# design.net
KiCad netlist of a schematic drawn in EasyEDA Pro
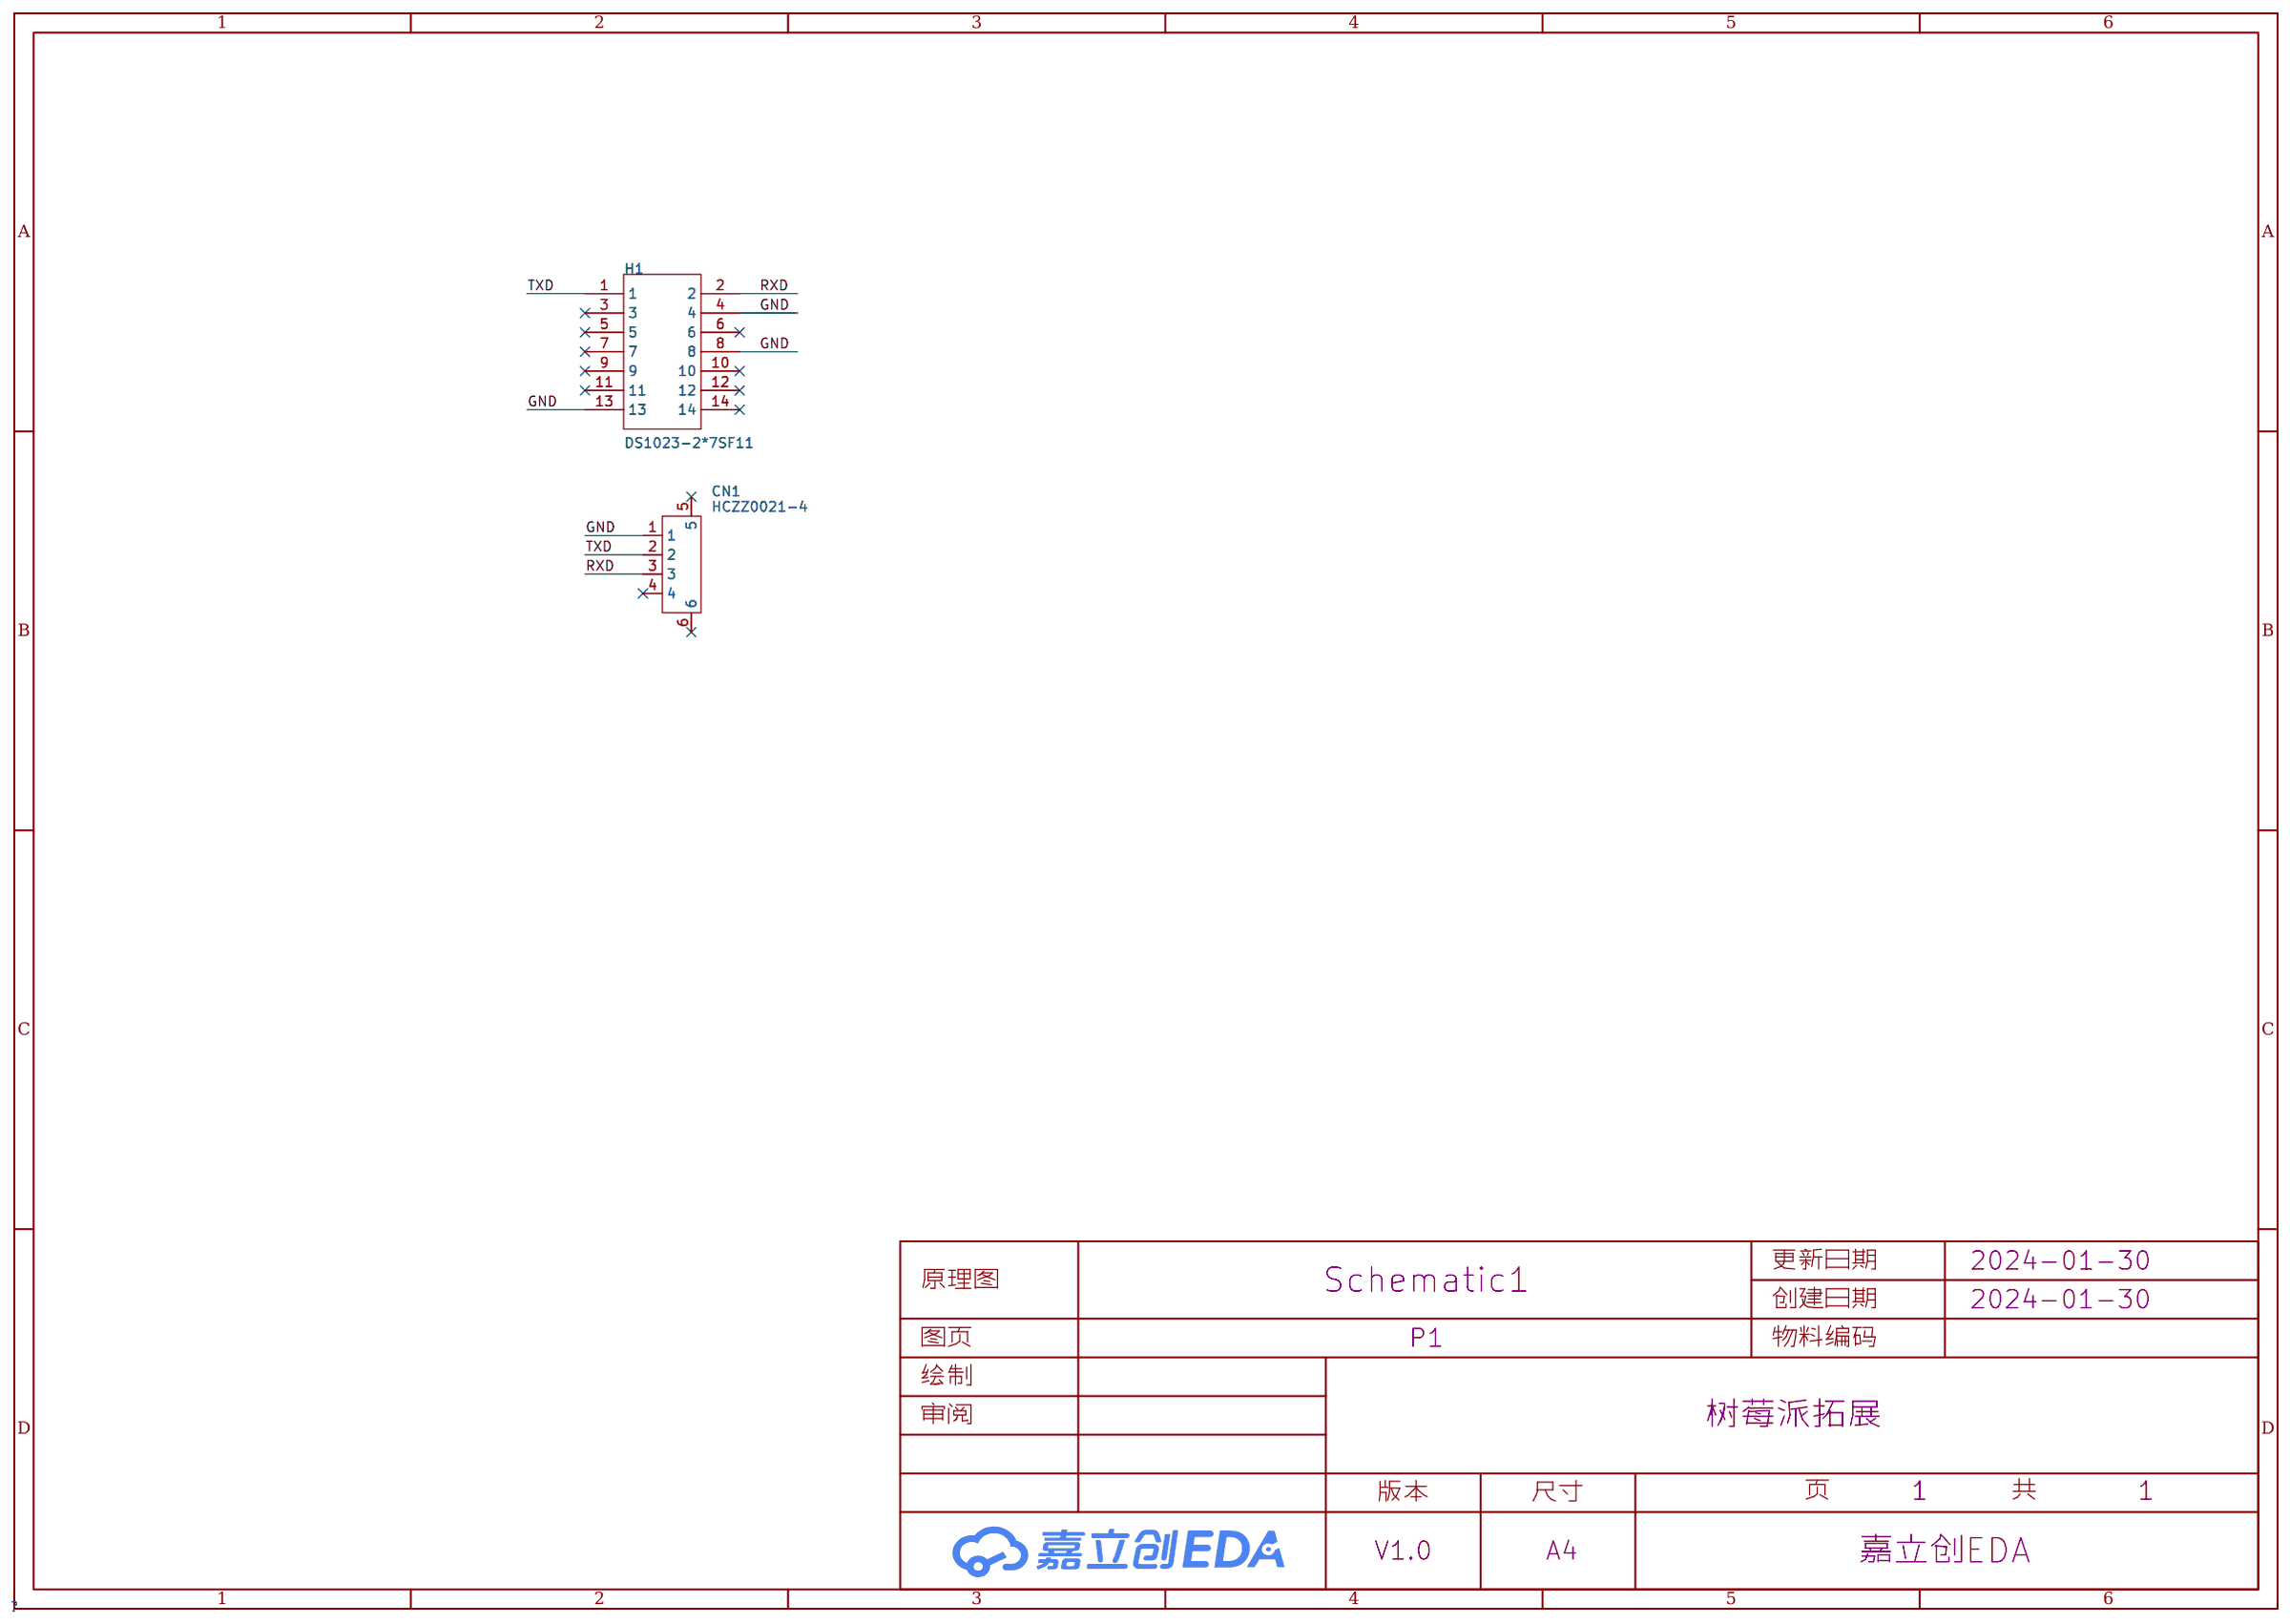
[diagram p0: schematic sheet]

(export (version "E")
  (design (tool "Eeschema 10.0.6"))
  (components
    (comp (ref "CN1")
      (value "HCZZ0021-4")
      (footprint "easyedapro:CONN-SMD_HCZZ0021-4")
      (fields (field (name "Manufacturer") "HC(虹成电子)"))
      (libsource (lib "easyedapro") (part "HCZZ0021-4"))
    )
    (comp (ref "H1")
      (value "DS1023-2*7SF11")
      (footprint "easyedapro:HDR-TH_14P-P2.54-V-F-R2-C7-S2.54-1")
      (description "插孔结构:2x7P;间距:2.54mm;行距:2.54mm;安装类型:直插;排数:双排;总孔位数:14P;塑高:-;触头材质:-;触头镀层:-;")
      (fields (field (name "Manufacturer") "CONNFLY"))
      (libsource (lib "easyedapro") (part "DS1023-2*7SF11"))
    )
  )
  (nets
    (net (code "1") (name "/GND") (class "Default")
      (node (ref "CN1") (pin "1") (pinfunction "1_1") (pintype "unspecified"))
      (node (ref "H1") (pin "13") (pinfunction "13_13") (pintype "unspecified"))
      (node (ref "H1") (pin "4") (pinfunction "4_4") (pintype "unspecified"))
      (node (ref "H1") (pin "8") (pinfunction "8_8") (pintype "unspecified"))
    )
    (net (code "2") (name "/RXD") (class "Default")
      (node (ref "CN1") (pin "3") (pinfunction "3_3") (pintype "unspecified"))
      (node (ref "H1") (pin "2") (pinfunction "2_2") (pintype "unspecified"))
    )
    (net (code "3") (name "/TXD") (class "Default")
      (node (ref "CN1") (pin "2") (pinfunction "2_2") (pintype "unspecified"))
      (node (ref "H1") (pin "1") (pinfunction "1_1") (pintype "unspecified"))
    )
    (net (code "4") (name "unconnected-(CN1-Pad4)") (class "Default")
      (node (ref "CN1") (pin "4") (pinfunction "4_4") (pintype "unspecified+no_connect"))
    )
    (net (code "5") (name "unconnected-(CN1-Pad5)") (class "Default")
      (node (ref "CN1") (pin "5") (pinfunction "5_5") (pintype "unspecified+no_connect"))
    )
    (net (code "6") (name "unconnected-(CN1-Pad6)") (class "Default")
      (node (ref "CN1") (pin "6") (pinfunction "6_6") (pintype "unspecified+no_connect"))
    )
    (net (code "7") (name "unconnected-(H1-Pad3)") (class "Default")
      (node (ref "H1") (pin "3") (pinfunction "3_3") (pintype "unspecified+no_connect"))
    )
    (net (code "8") (name "unconnected-(H1-Pad5)") (class "Default")
      (node (ref "H1") (pin "5") (pinfunction "5_5") (pintype "unspecified+no_connect"))
    )
    (net (code "9") (name "unconnected-(H1-Pad6)") (class "Default")
      (node (ref "H1") (pin "6") (pinfunction "6_6") (pintype "unspecified+no_connect"))
    )
    (net (code "10") (name "unconnected-(H1-Pad7)") (class "Default")
      (node (ref "H1") (pin "7") (pinfunction "7_7") (pintype "unspecified+no_connect"))
    )
    (net (code "11") (name "unconnected-(H1-Pad9)") (class "Default")
      (node (ref "H1") (pin "9") (pinfunction "9_9") (pintype "unspecified+no_connect"))
    )
    (net (code "12") (name "unconnected-(H1-Pad10)") (class "Default")
      (node (ref "H1") (pin "10") (pinfunction "10_10") (pintype "unspecified+no_connect"))
    )
    (net (code "13") (name "unconnected-(H1-Pad11)") (class "Default")
      (node (ref "H1") (pin "11") (pinfunction "11_11") (pintype "unspecified+no_connect"))
    )
    (net (code "14") (name "unconnected-(H1-Pad12)") (class "Default")
      (node (ref "H1") (pin "12") (pinfunction "12_12") (pintype "unspecified+no_connect"))
    )
    (net (code "15") (name "unconnected-(H1-Pad14)") (class "Default")
      (node (ref "H1") (pin "14") (pinfunction "14_14") (pintype "unspecified+no_connect"))
    )
  )
)
